# AIM2_-_UART_LEDS_REVB.net
KiCad netlist of a schematic drawn in Altium Designer
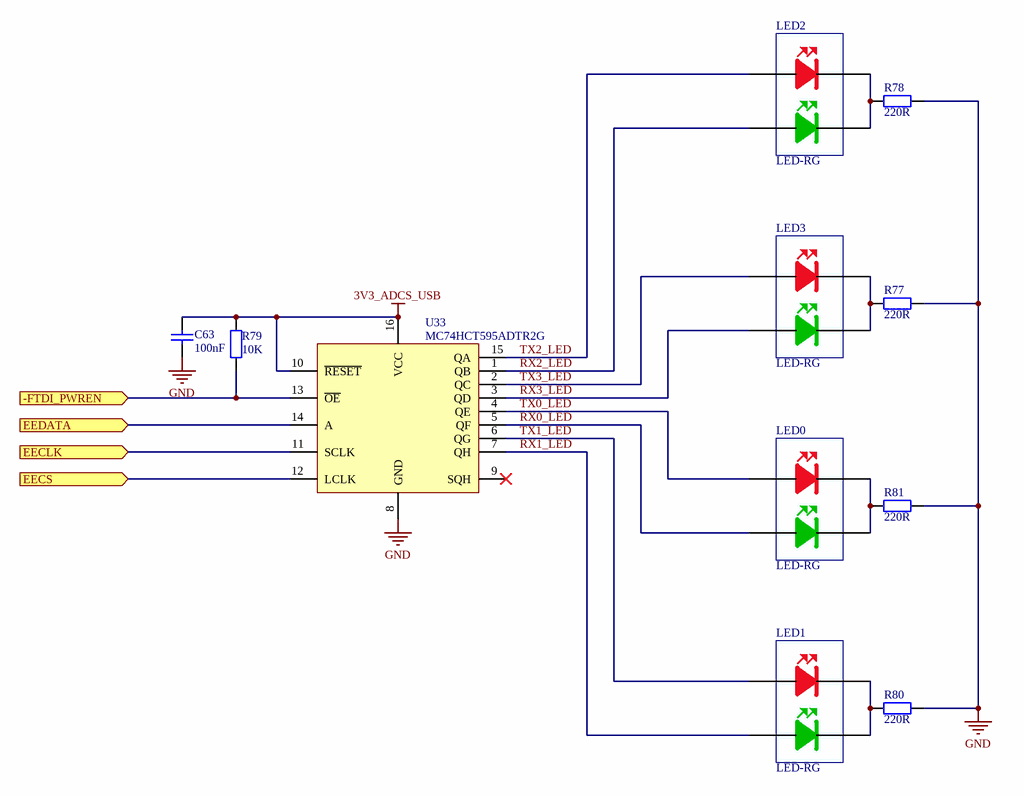
[diagram p0: AIM2 - UART LEDS REVB.SchDoc]

(export (version "E")
  (design (tool "Eeschema 10.0.6"))
  (components
    (comp (ref "C63")
      (value "100nF")
      (footprint "0603 CAP")
      (description "Capacitor 100nF 0603 X7R 50V 5%")
      (libsource (lib "Supernova passives") (part "Capacitor 100nF 0603"))
    )
    (comp (ref "LED0")
      (value "LED-RG")
      (footprint "LED SMT RG")
      (description "LED Red, Green 0805")
      (libsource (lib "Supernova passives") (part "LED RED/GREEN 0805"))
    )
    (comp (ref "LED1")
      (value "LED-RG")
      (footprint "LED SMT RG")
      (description "LED Red, Green 0805")
      (libsource (lib "Supernova passives") (part "LED RED/GREEN 0805"))
    )
    (comp (ref "LED2")
      (value "LED-RG")
      (footprint "LED SMT RG")
      (description "LED Red, Green 0805")
      (libsource (lib "Supernova passives") (part "LED RED/GREEN 0805"))
    )
    (comp (ref "LED3")
      (value "LED-RG")
      (footprint "LED SMT RG")
      (description "LED Red, Green 0805")
      (libsource (lib "Supernova passives") (part "LED RED/GREEN 0805"))
    )
    (comp (ref "R77")
      (value "220R")
      (footprint "0805 RES")
      (description "Resistor 220R 0805 0.125W 1%")
      (libsource (lib "Supernova passives") (part "Resistor 220R 0805"))
    )
    (comp (ref "R78")
      (value "220R")
      (footprint "0805 RES")
      (description "Resistor 220R 0805 0.125W 1%")
      (libsource (lib "Supernova passives") (part "Resistor 220R 0805"))
    )
    (comp (ref "R79")
      (value "10K")
      (footprint "0805 RES")
      (description "Resistor 10K 0805 0.125W 1%")
      (libsource (lib "Supernova passives") (part "Resistor 10K 0805"))
    )
    (comp (ref "R80")
      (value "220R")
      (footprint "0805 RES")
      (description "Resistor 220R 0805 0.125W 1%")
      (libsource (lib "Supernova passives") (part "Resistor 220R 0805"))
    )
    (comp (ref "R81")
      (value "220R")
      (footprint "0805 RES")
      (description "Resistor 220R 0805 0.125W 1%")
      (libsource (lib "Supernova passives") (part "Resistor 220R 0805"))
    )
    (comp (ref "U33")
      (value "MC74HCT595ADTR2G")
      (footprint "TSOP-16")
      (description "IC Shift Register")
      (libsource (lib "Supernova") (part "MC74HCT595ADTR2G"))
    )
  )
  (nets
    (net (code "1") (name "/-FTDI_PWREN") (class "Default")
      (node (ref "R79") (pin "1") (pinfunction "1_1") (pintype "passive"))
      (node (ref "U33") (pin "13") (pinfunction "~{OE}_13") (pintype "passive"))
    )
    (net (code "2") (name "/EECLK") (class "Default")
      (node (ref "U33") (pin "11") (pinfunction "SCLK_11") (pintype "passive"))
    )
    (net (code "3") (name "/EECS") (class "Default")
      (node (ref "U33") (pin "12") (pinfunction "LCLK_12") (pintype "passive"))
    )
    (net (code "4") (name "/EEDATA") (class "Default")
      (node (ref "U33") (pin "14") (pinfunction "A_14") (pintype "passive"))
    )
    (net (code "5") (name "/RX0_LED") (class "Default")
      (node (ref "LED0") (pin "4") (pinfunction "4_4") (pintype "passive"))
      (node (ref "U33") (pin "5") (pinfunction "QF_5") (pintype "passive"))
    )
    (net (code "6") (name "/RX1_LED") (class "Default")
      (node (ref "LED1") (pin "4") (pinfunction "4_4") (pintype "passive"))
      (node (ref "U33") (pin "7") (pinfunction "QH_7") (pintype "passive"))
    )
    (net (code "7") (name "/RX2_LED") (class "Default")
      (node (ref "LED2") (pin "4") (pinfunction "4_4") (pintype "passive"))
      (node (ref "U33") (pin "1") (pinfunction "QB_1") (pintype "passive"))
    )
    (net (code "8") (name "/RX3_LED") (class "Default")
      (node (ref "LED3") (pin "4") (pinfunction "4_4") (pintype "passive"))
      (node (ref "U33") (pin "3") (pinfunction "QD_3") (pintype "passive"))
    )
    (net (code "9") (name "/TX0_LED") (class "Default")
      (node (ref "LED0") (pin "1") (pinfunction "1_1") (pintype "passive"))
      (node (ref "U33") (pin "4") (pinfunction "QE_4") (pintype "passive"))
    )
    (net (code "10") (name "/TX1_LED") (class "Default")
      (node (ref "LED1") (pin "1") (pinfunction "1_1") (pintype "passive"))
      (node (ref "U33") (pin "6") (pinfunction "QG_6") (pintype "passive"))
    )
    (net (code "11") (name "/TX2_LED") (class "Default")
      (node (ref "LED2") (pin "1") (pinfunction "1_1") (pintype "passive"))
      (node (ref "U33") (pin "15") (pinfunction "QA_15") (pintype "passive"))
    )
    (net (code "12") (name "/TX3_LED") (class "Default")
      (node (ref "LED3") (pin "1") (pinfunction "1_1") (pintype "passive"))
      (node (ref "U33") (pin "2") (pinfunction "QC_2") (pintype "passive"))
    )
    (net (code "13") (name "3V3_ADCS_USB") (class "Default")
      (node (ref "C63") (pin "2") (pinfunction "2_2") (pintype "passive"))
      (node (ref "R79") (pin "2") (pinfunction "2_2") (pintype "passive"))
      (node (ref "U33") (pin "10") (pinfunction "~{RESET}_10") (pintype "passive"))
      (node (ref "U33") (pin "16") (pinfunction "VCC_16") (pintype "passive"))
    )
    (net (code "14") (name "GND") (class "Default")
      (node (ref "C63") (pin "1") (pinfunction "1_1") (pintype "passive"))
      (node (ref "R77") (pin "2") (pinfunction "2_2") (pintype "passive"))
      (node (ref "R78") (pin "2") (pinfunction "2_2") (pintype "passive"))
      (node (ref "R80") (pin "2") (pinfunction "2_2") (pintype "passive"))
      (node (ref "R81") (pin "2") (pinfunction "2_2") (pintype "passive"))
      (node (ref "U33") (pin "8") (pinfunction "GND_8") (pintype "passive"))
    )
    (net (code "15") (name "Net-(LED0-Pad2)") (class "Default")
      (node (ref "LED0") (pin "2") (pinfunction "2_2") (pintype "passive"))
      (node (ref "LED0") (pin "3") (pinfunction "3_3") (pintype "passive"))
      (node (ref "R81") (pin "1") (pinfunction "1_1") (pintype "passive"))
    )
    (net (code "16") (name "Net-(LED1-Pad2)") (class "Default")
      (node (ref "LED1") (pin "2") (pinfunction "2_2") (pintype "passive"))
      (node (ref "LED1") (pin "3") (pinfunction "3_3") (pintype "passive"))
      (node (ref "R80") (pin "1") (pinfunction "1_1") (pintype "passive"))
    )
    (net (code "17") (name "Net-(LED2-Pad2)") (class "Default")
      (node (ref "LED2") (pin "2") (pinfunction "2_2") (pintype "passive"))
      (node (ref "LED2") (pin "3") (pinfunction "3_3") (pintype "passive"))
      (node (ref "R78") (pin "1") (pinfunction "1_1") (pintype "passive"))
    )
    (net (code "18") (name "Net-(LED3-Pad2)") (class "Default")
      (node (ref "LED3") (pin "2") (pinfunction "2_2") (pintype "passive"))
      (node (ref "LED3") (pin "3") (pinfunction "3_3") (pintype "passive"))
      (node (ref "R77") (pin "1") (pinfunction "1_1") (pintype "passive"))
    )
    (net (code "19") (name "unconnected-(U33-SQH-Pad9)") (class "Default")
      (node (ref "U33") (pin "9") (pinfunction "SQH_9") (pintype "passive+no_connect"))
    )
  )
)
